# beagle_cnc_1_0.net
KiCad netlist of a schematic drawn in EAGLE
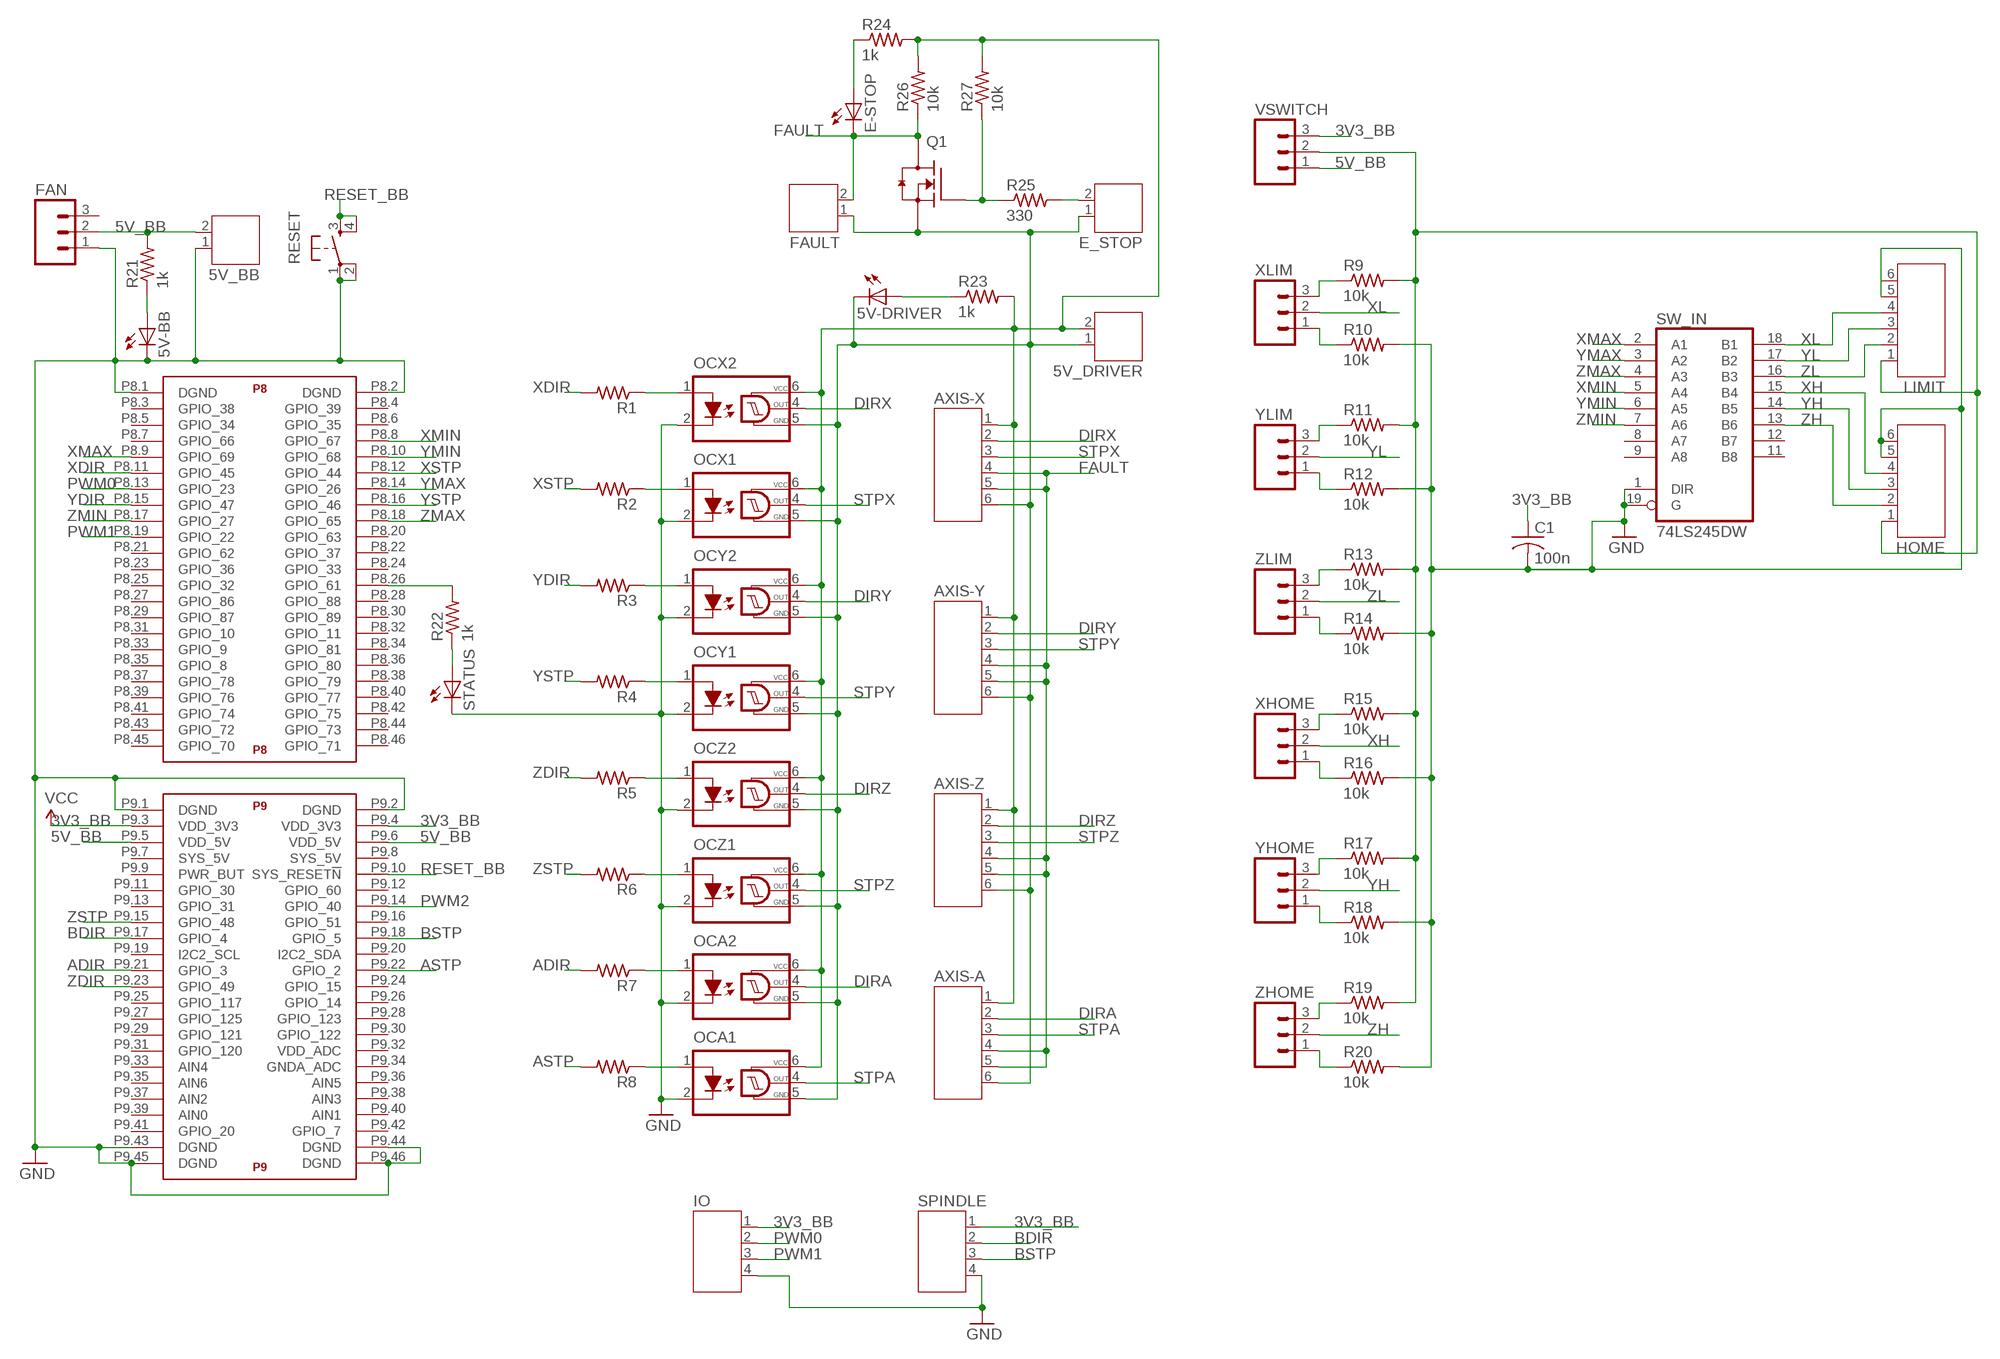
[diagram p0: schematic, sheet 1]

(export (version "E")
  (design (tool "Eeschema 10.0.6"))
  (components
    (comp (ref "5V-BB")
      (value "LEDCHIP-LED0603")
      (footprint "eagle-import:CHIP-LED0603")
      (libsource (lib "eagle-import") (part "LEDCHIP-LED0603"))
    )
    (comp (ref "5V-DRIVER")
      (value "LEDCHIP-LED0603")
      (footprint "eagle-import:CHIP-LED0603")
      (libsource (lib "eagle-import") (part "LEDCHIP-LED0603"))
    )
    (comp (ref "5V_BB")
      (value "JST-PH2")
      (footprint "eagle-import:JST-PH2")
      (libsource (lib "eagle-import") (part "JST-PH2"))
    )
    (comp (ref "5V_DRIVER")
      (value "JST-PH2")
      (footprint "eagle-import:JST-PH2")
      (libsource (lib "eagle-import") (part "JST-PH2"))
    )
    (comp (ref "AXIS-A")
      (value "JST-PH6")
      (footprint "eagle-import:JST-PH6")
      (libsource (lib "eagle-import") (part "JST-PH6"))
    )
    (comp (ref "AXIS-X")
      (value "JST-PH6")
      (footprint "eagle-import:JST-PH6")
      (libsource (lib "eagle-import") (part "JST-PH6"))
    )
    (comp (ref "AXIS-Y")
      (value "JST-PH6")
      (footprint "eagle-import:JST-PH6")
      (libsource (lib "eagle-import") (part "JST-PH6"))
    )
    (comp (ref "AXIS-Z")
      (value "JST-PH6")
      (footprint "eagle-import:JST-PH6")
      (libsource (lib "eagle-import") (part "JST-PH6"))
    )
    (comp (ref "C1")
      (value "100n")
      (footprint "eagle-import:C0603")
      (libsource (lib "eagle-import") (part "C-USC0603"))
    )
    (comp (ref "E-STOP")
      (value "LEDCHIP-LED0603")
      (footprint "eagle-import:CHIP-LED0603")
      (libsource (lib "eagle-import") (part "LEDCHIP-LED0603"))
    )
    (comp (ref "E_STOP")
      (value "JST-PH2")
      (footprint "eagle-import:JST-PH2")
      (libsource (lib "eagle-import") (part "JST-PH2"))
    )
    (comp (ref "FAN")
      (value "M03POLAR")
      (footprint "eagle-import:MOLEX-1X3")
      (libsource (lib "eagle-import") (part "M03POLAR"))
    )
    (comp (ref "FAULT")
      (value "JST-PH2")
      (footprint "eagle-import:JST-PH2")
      (libsource (lib "eagle-import") (part "JST-PH2"))
    )
    (comp (ref "HOME")
      (value "JST-PH6")
      (footprint "eagle-import:JST-PH6")
      (libsource (lib "eagle-import") (part "JST-PH6"))
    )
    (comp (ref "IO")
      (value "JST-PH4")
      (footprint "eagle-import:JST-PH4")
      (libsource (lib "eagle-import") (part "JST-PH4"))
    )
    (comp (ref "LIMIT")
      (value "JST-PH6")
      (footprint "eagle-import:JST-PH6")
      (libsource (lib "eagle-import") (part "JST-PH6"))
    )
    (comp (ref "OCA1")
      (value "H11L1MS")
      (footprint "eagle-import:DIL6-SMD")
      (libsource (lib "eagle-import") (part "H11LMS1"))
    )
    (comp (ref "OCA2")
      (value "H11L1MS")
      (footprint "eagle-import:DIL6-SMD")
      (libsource (lib "eagle-import") (part "H11LMS1"))
    )
    (comp (ref "OCX1")
      (value "H11L1MS")
      (footprint "eagle-import:DIL6-SMD")
      (libsource (lib "eagle-import") (part "H11LMS1"))
    )
    (comp (ref "OCX2")
      (value "H11L1MS")
      (footprint "eagle-import:DIL6-SMD")
      (libsource (lib "eagle-import") (part "H11LMS1"))
    )
    (comp (ref "OCY1")
      (value "H11L1MS")
      (footprint "eagle-import:DIL6-SMD")
      (libsource (lib "eagle-import") (part "H11LMS1"))
    )
    (comp (ref "OCY2")
      (value "H11L1MS")
      (footprint "eagle-import:DIL6-SMD")
      (libsource (lib "eagle-import") (part "H11LMS1"))
    )
    (comp (ref "OCZ1")
      (value "H11L1MS")
      (footprint "eagle-import:DIL6-SMD")
      (libsource (lib "eagle-import") (part "H11LMS1"))
    )
    (comp (ref "OCZ2")
      (value "H11L1MS")
      (footprint "eagle-import:DIL6-SMD")
      (libsource (lib "eagle-import") (part "H11LMS1"))
    )
    (comp (ref "Q1")
      (value "MOSFET-NCH_SOT-23")
      (footprint "eagle-import:SOT95P280X135-3N")
      (libsource (lib "eagle-import") (part "MOSFET-NCH_SOT-23"))
    )
    (comp (ref "R1")
      (value "R-US_R0603")
      (footprint "eagle-import:R0603")
      (libsource (lib "eagle-import") (part "R-US_R0603"))
    )
    (comp (ref "R2")
      (value "R-US_R0603")
      (footprint "eagle-import:R0603")
      (libsource (lib "eagle-import") (part "R-US_R0603"))
    )
    (comp (ref "R3")
      (value "R-US_R0603")
      (footprint "eagle-import:R0603")
      (libsource (lib "eagle-import") (part "R-US_R0603"))
    )
    (comp (ref "R4")
      (value "R-US_R0603")
      (footprint "eagle-import:R0603")
      (libsource (lib "eagle-import") (part "R-US_R0603"))
    )
    (comp (ref "R5")
      (value "R-US_R0603")
      (footprint "eagle-import:R0603")
      (libsource (lib "eagle-import") (part "R-US_R0603"))
    )
    (comp (ref "R6")
      (value "R-US_R0603")
      (footprint "eagle-import:R0603")
      (libsource (lib "eagle-import") (part "R-US_R0603"))
    )
    (comp (ref "R7")
      (value "R-US_R0603")
      (footprint "eagle-import:R0603")
      (libsource (lib "eagle-import") (part "R-US_R0603"))
    )
    (comp (ref "R8")
      (value "R-US_R0603")
      (footprint "eagle-import:R0603")
      (libsource (lib "eagle-import") (part "R-US_R0603"))
    )
    (comp (ref "R9")
      (value "10k")
      (footprint "eagle-import:R0603")
      (libsource (lib "eagle-import") (part "R-US_R0603"))
    )
    (comp (ref "R10")
      (value "10k")
      (footprint "eagle-import:R0603")
      (libsource (lib "eagle-import") (part "R-US_R0603"))
    )
    (comp (ref "R11")
      (value "10k")
      (footprint "eagle-import:R0603")
      (libsource (lib "eagle-import") (part "R-US_R0603"))
    )
    (comp (ref "R12")
      (value "10k")
      (footprint "eagle-import:R0603")
      (libsource (lib "eagle-import") (part "R-US_R0603"))
    )
    (comp (ref "R13")
      (value "10k")
      (footprint "eagle-import:R0603")
      (libsource (lib "eagle-import") (part "R-US_R0603"))
    )
    (comp (ref "R14")
      (value "10k")
      (footprint "eagle-import:R0603")
      (libsource (lib "eagle-import") (part "R-US_R0603"))
    )
    (comp (ref "R15")
      (value "10k")
      (footprint "eagle-import:R0603")
      (libsource (lib "eagle-import") (part "R-US_R0603"))
    )
    (comp (ref "R16")
      (value "10k")
      (footprint "eagle-import:R0603")
      (libsource (lib "eagle-import") (part "R-US_R0603"))
    )
    (comp (ref "R17")
      (value "10k")
      (footprint "eagle-import:R0603")
      (libsource (lib "eagle-import") (part "R-US_R0603"))
    )
    (comp (ref "R18")
      (value "10k")
      (footprint "eagle-import:R0603")
      (libsource (lib "eagle-import") (part "R-US_R0603"))
    )
    (comp (ref "R19")
      (value "10k")
      (footprint "eagle-import:R0603")
      (libsource (lib "eagle-import") (part "R-US_R0603"))
    )
    (comp (ref "R20")
      (value "10k")
      (footprint "eagle-import:R0603")
      (libsource (lib "eagle-import") (part "R-US_R0603"))
    )
    (comp (ref "R21")
      (value "1k")
      (footprint "eagle-import:R0603")
      (libsource (lib "eagle-import") (part "R-US_R0603"))
    )
    (comp (ref "R22")
      (value "1k")
      (footprint "eagle-import:R0603")
      (libsource (lib "eagle-import") (part "R-US_R0603"))
    )
    (comp (ref "R23")
      (value "1k")
      (footprint "eagle-import:R0603")
      (libsource (lib "eagle-import") (part "R-US_R0603"))
    )
    (comp (ref "R24")
      (value "1k")
      (footprint "eagle-import:R0603")
      (libsource (lib "eagle-import") (part "R-US_R0603"))
    )
    (comp (ref "R25")
      (value "330")
      (footprint "eagle-import:R0603")
      (libsource (lib "eagle-import") (part "R-US_R0603"))
    )
    (comp (ref "R26")
      (value "10k")
      (footprint "eagle-import:R0603")
      (libsource (lib "eagle-import") (part "R-US_R0603"))
    )
    (comp (ref "R27")
      (value "10k")
      (footprint "eagle-import:R0603")
      (libsource (lib "eagle-import") (part "R-US_R0603"))
    )
    (comp (ref "RESET")
      (value "TAC_SWITCHSMD")
      (footprint "eagle-import:TACTILE-SWITCH-SMD")
      (libsource (lib "eagle-import") (part "TAC_SWITCHSMD"))
    )
    (comp (ref "SPINDLE")
      (value "JST-PH4")
      (footprint "eagle-import:JST-PH4")
      (libsource (lib "eagle-import") (part "JST-PH4"))
    )
    (comp (ref "STATUS")
      (value "LEDCHIP-LED0603")
      (footprint "eagle-import:CHIP-LED0603")
      (libsource (lib "eagle-import") (part "LEDCHIP-LED0603"))
    )
    (comp (ref "SW_IN")
      (value "74LS245DW")
      (footprint "eagle-import:SO20W")
      (libsource (lib "eagle-import") (part "74245DWLS"))
    )
    (comp (ref "U$1")
      (value "BEAGLE_BONE_BLACK_CAPE")
      (footprint "eagle-import:BEAGLE_BONE_BLACK_CAPE")
      (libsource (lib "eagle-import") (part "BEAGLE_BONE_BLACK_CAPE"))
    )
    (comp (ref "VSWITCH")
      (value "M03PTH")
      (footprint "eagle-import:1X03")
      (libsource (lib "eagle-import") (part "M03PTH"))
    )
    (comp (ref "XHOME")
      (value "M03PTH")
      (footprint "eagle-import:1X03")
      (libsource (lib "eagle-import") (part "M03PTH"))
    )
    (comp (ref "XLIM")
      (value "M03PTH")
      (footprint "eagle-import:1X03")
      (libsource (lib "eagle-import") (part "M03PTH"))
    )
    (comp (ref "YHOME")
      (value "M03PTH")
      (footprint "eagle-import:1X03")
      (libsource (lib "eagle-import") (part "M03PTH"))
    )
    (comp (ref "YLIM")
      (value "M03PTH")
      (footprint "eagle-import:1X03")
      (libsource (lib "eagle-import") (part "M03PTH"))
    )
    (comp (ref "ZHOME")
      (value "M03PTH")
      (footprint "eagle-import:1X03")
      (libsource (lib "eagle-import") (part "M03PTH"))
    )
    (comp (ref "ZLIM")
      (value "M03PTH")
      (footprint "eagle-import:1X03")
      (libsource (lib "eagle-import") (part "M03PTH"))
    )
  )
  (nets
    (net (code "1") (name "/5V_BB") (class "Default")
      (node (ref "5V_BB") (pin "2") (pinfunction "2_2") (pintype "passive"))
      (node (ref "FAN") (pin "2") (pinfunction "2_2") (pintype "passive"))
      (node (ref "R21") (pin "2") (pinfunction "2_2") (pintype "passive"))
      (node (ref "U$1") (pin "P9.5") (pinfunction "VDD_5V_P9.5") (pintype "bidirectional"))
      (node (ref "U$1") (pin "P9.6") (pinfunction "VDD_5V_P9.6") (pintype "bidirectional"))
      (node (ref "VSWITCH") (pin "1") (pinfunction "1_1") (pintype "passive"))
    )
    (net (code "2") (name "/ADIR") (class "Default")
      (node (ref "R7") (pin "2") (pinfunction "2_2") (pintype "passive"))
      (node (ref "U$1") (pin "P9.21") (pinfunction "GPIO_3_P9.21") (pintype "bidirectional"))
    )
    (net (code "3") (name "/ASTP") (class "Default")
      (node (ref "R8") (pin "2") (pinfunction "2_2") (pintype "passive"))
      (node (ref "U$1") (pin "P9.22") (pinfunction "GPIO_2_P9.22") (pintype "bidirectional"))
    )
    (net (code "4") (name "/BDIR") (class "Default")
      (node (ref "SPINDLE") (pin "2") (pinfunction "2_2") (pintype "passive"))
      (node (ref "U$1") (pin "P9.17") (pinfunction "GPIO_4_P9.17") (pintype "bidirectional"))
    )
    (net (code "5") (name "/BSTP") (class "Default")
      (node (ref "SPINDLE") (pin "3") (pinfunction "3_3") (pintype "passive"))
      (node (ref "U$1") (pin "P9.18") (pinfunction "GPIO_5_P9.18") (pintype "bidirectional"))
    )
    (net (code "6") (name "/DIRA") (class "Default")
      (node (ref "AXIS-A") (pin "2") (pinfunction "2_2") (pintype "passive"))
      (node (ref "OCA2") (pin "4") (pinfunction "OUT_4") (pintype "output"))
    )
    (net (code "7") (name "/DIRX") (class "Default")
      (node (ref "AXIS-X") (pin "2") (pinfunction "2_2") (pintype "passive"))
      (node (ref "OCX2") (pin "4") (pinfunction "OUT_4") (pintype "output"))
    )
    (net (code "8") (name "/DIRY") (class "Default")
      (node (ref "AXIS-Y") (pin "2") (pinfunction "2_2") (pintype "passive"))
      (node (ref "OCY2") (pin "4") (pinfunction "OUT_4") (pintype "output"))
    )
    (net (code "9") (name "/DIRZ") (class "Default")
      (node (ref "AXIS-Z") (pin "2") (pinfunction "2_2") (pintype "passive"))
      (node (ref "OCZ2") (pin "4") (pinfunction "OUT_4") (pintype "output"))
    )
    (net (code "10") (name "/FAULT") (class "Default")
      (node (ref "AXIS-A") (pin "4") (pinfunction "4_4") (pintype "passive"))
      (node (ref "AXIS-A") (pin "5") (pinfunction "5_5") (pintype "passive"))
      (node (ref "AXIS-X") (pin "4") (pinfunction "4_4") (pintype "passive"))
      (node (ref "AXIS-X") (pin "5") (pinfunction "5_5") (pintype "passive"))
      (node (ref "AXIS-Y") (pin "4") (pinfunction "4_4") (pintype "passive"))
      (node (ref "AXIS-Y") (pin "5") (pinfunction "5_5") (pintype "passive"))
      (node (ref "AXIS-Z") (pin "4") (pinfunction "4_4") (pintype "passive"))
      (node (ref "AXIS-Z") (pin "5") (pinfunction "5_5") (pintype "passive"))
      (node (ref "E-STOP") (pin "C") (pinfunction "C_C") (pintype "passive"))
      (node (ref "FAULT") (pin "2") (pinfunction "2_2") (pintype "passive"))
      (node (ref "Q1") (pin "3") (pinfunction "D_3") (pintype "passive"))
      (node (ref "R26") (pin "1") (pinfunction "1_1") (pintype "passive"))
    )
    (net (code "11") (name "/PWM0") (class "Default")
      (node (ref "IO") (pin "2") (pinfunction "2_2") (pintype "passive"))
      (node (ref "U$1") (pin "P8.13") (pinfunction "GPIO_23_P8.13") (pintype "bidirectional"))
    )
    (net (code "12") (name "/PWM1") (class "Default")
      (node (ref "IO") (pin "3") (pinfunction "3_3") (pintype "passive"))
      (node (ref "U$1") (pin "P8.19") (pinfunction "GPIO_22_P8.19") (pintype "bidirectional"))
    )
    (net (code "13") (name "/PWM2") (class "Default")
      (node (ref "U$1") (pin "P9.14") (pinfunction "GPIO_40_P9.14") (pintype "bidirectional"))
    )
    (net (code "14") (name "/RESET_BB") (class "Default")
      (node (ref "RESET") (pin "3") (pinfunction "3_3") (pintype "passive"))
      (node (ref "RESET") (pin "4") (pinfunction "4_4") (pintype "passive"))
      (node (ref "U$1") (pin "P9.10") (pinfunction "SYS_RESET~{N}_P9.10") (pintype "bidirectional"))
    )
    (net (code "15") (name "/STPA") (class "Default")
      (node (ref "AXIS-A") (pin "3") (pinfunction "3_3") (pintype "passive"))
      (node (ref "OCA1") (pin "4") (pinfunction "OUT_4") (pintype "output"))
    )
    (net (code "16") (name "/STPX") (class "Default")
      (node (ref "AXIS-X") (pin "3") (pinfunction "3_3") (pintype "passive"))
      (node (ref "OCX1") (pin "4") (pinfunction "OUT_4") (pintype "output"))
    )
    (net (code "17") (name "/STPY") (class "Default")
      (node (ref "AXIS-Y") (pin "3") (pinfunction "3_3") (pintype "passive"))
      (node (ref "OCY1") (pin "4") (pinfunction "OUT_4") (pintype "output"))
    )
    (net (code "18") (name "/STPZ") (class "Default")
      (node (ref "AXIS-Z") (pin "3") (pinfunction "3_3") (pintype "passive"))
      (node (ref "OCZ1") (pin "4") (pinfunction "OUT_4") (pintype "output"))
    )
    (net (code "19") (name "/XDIR") (class "Default")
      (node (ref "R1") (pin "2") (pinfunction "2_2") (pintype "passive"))
      (node (ref "U$1") (pin "P8.11") (pinfunction "GPIO_45_P8.11") (pintype "bidirectional"))
    )
    (net (code "20") (name "/XH") (class "Default")
      (node (ref "HOME") (pin "4") (pinfunction "4_4") (pintype "passive"))
      (node (ref "SW_IN") (pin "15") (pinfunction "B4_15") (pintype "bidirectional"))
      (node (ref "XHOME") (pin "2") (pinfunction "2_2") (pintype "passive"))
    )
    (net (code "21") (name "/XL") (class "Default")
      (node (ref "LIMIT") (pin "4") (pinfunction "4_4") (pintype "passive"))
      (node (ref "SW_IN") (pin "18") (pinfunction "B1_18") (pintype "bidirectional"))
      (node (ref "XLIM") (pin "2") (pinfunction "2_2") (pintype "passive"))
    )
    (net (code "22") (name "/XMAX") (class "Default")
      (node (ref "SW_IN") (pin "2") (pinfunction "A1_2") (pintype "bidirectional"))
      (node (ref "U$1") (pin "P8.9") (pinfunction "GPIO_69_P8.9") (pintype "bidirectional"))
    )
    (net (code "23") (name "/XMIN") (class "Default")
      (node (ref "SW_IN") (pin "5") (pinfunction "A4_5") (pintype "bidirectional"))
      (node (ref "U$1") (pin "P8.8") (pinfunction "GPIO_67_P8.8") (pintype "bidirectional"))
    )
    (net (code "24") (name "/XSTP") (class "Default")
      (node (ref "R2") (pin "2") (pinfunction "2_2") (pintype "passive"))
      (node (ref "U$1") (pin "P8.12") (pinfunction "GPIO_44_P8.12") (pintype "bidirectional"))
    )
    (net (code "25") (name "/YDIR") (class "Default")
      (node (ref "R3") (pin "2") (pinfunction "2_2") (pintype "passive"))
      (node (ref "U$1") (pin "P8.15") (pinfunction "GPIO_47_P8.15") (pintype "bidirectional"))
    )
    (net (code "26") (name "/YH") (class "Default")
      (node (ref "HOME") (pin "3") (pinfunction "3_3") (pintype "passive"))
      (node (ref "SW_IN") (pin "14") (pinfunction "B5_14") (pintype "bidirectional"))
      (node (ref "YHOME") (pin "2") (pinfunction "2_2") (pintype "passive"))
    )
    (net (code "27") (name "/YL") (class "Default")
      (node (ref "LIMIT") (pin "3") (pinfunction "3_3") (pintype "passive"))
      (node (ref "SW_IN") (pin "17") (pinfunction "B2_17") (pintype "bidirectional"))
      (node (ref "YLIM") (pin "2") (pinfunction "2_2") (pintype "passive"))
    )
    (net (code "28") (name "/YMAX") (class "Default")
      (node (ref "SW_IN") (pin "3") (pinfunction "A2_3") (pintype "bidirectional"))
      (node (ref "U$1") (pin "P8.14") (pinfunction "GPIO_26_P8.14") (pintype "bidirectional"))
    )
    (net (code "29") (name "/YMIN") (class "Default")
      (node (ref "SW_IN") (pin "6") (pinfunction "A5_6") (pintype "bidirectional"))
      (node (ref "U$1") (pin "P8.10") (pinfunction "GPIO_68_P8.10") (pintype "bidirectional"))
    )
    (net (code "30") (name "/YSTP") (class "Default")
      (node (ref "R4") (pin "2") (pinfunction "2_2") (pintype "passive"))
      (node (ref "U$1") (pin "P8.16") (pinfunction "GPIO_46_P8.16") (pintype "bidirectional"))
    )
    (net (code "31") (name "/ZDIR") (class "Default")
      (node (ref "R5") (pin "2") (pinfunction "2_2") (pintype "passive"))
      (node (ref "U$1") (pin "P9.23") (pinfunction "GPIO_49_P9.23") (pintype "bidirectional"))
    )
    (net (code "32") (name "/ZH") (class "Default")
      (node (ref "HOME") (pin "2") (pinfunction "2_2") (pintype "passive"))
      (node (ref "SW_IN") (pin "13") (pinfunction "B6_13") (pintype "bidirectional"))
      (node (ref "ZHOME") (pin "2") (pinfunction "2_2") (pintype "passive"))
    )
    (net (code "33") (name "/ZL") (class "Default")
      (node (ref "LIMIT") (pin "2") (pinfunction "2_2") (pintype "passive"))
      (node (ref "SW_IN") (pin "16") (pinfunction "B3_16") (pintype "bidirectional"))
      (node (ref "ZLIM") (pin "2") (pinfunction "2_2") (pintype "passive"))
    )
    (net (code "34") (name "/ZMAX") (class "Default")
      (node (ref "SW_IN") (pin "4") (pinfunction "A3_4") (pintype "bidirectional"))
      (node (ref "U$1") (pin "P8.18") (pinfunction "GPIO_65_P8.18") (pintype "bidirectional"))
    )
    (net (code "35") (name "/ZMIN") (class "Default")
      (node (ref "SW_IN") (pin "7") (pinfunction "A6_7") (pintype "bidirectional"))
      (node (ref "U$1") (pin "P8.17") (pinfunction "GPIO_27_P8.17") (pintype "bidirectional"))
    )
    (net (code "36") (name "/ZSTP") (class "Default")
      (node (ref "R6") (pin "2") (pinfunction "2_2") (pintype "passive"))
      (node (ref "U$1") (pin "P9.15") (pinfunction "GPIO_48_P9.15") (pintype "bidirectional"))
    )
    (net (code "37") (name "GND") (class "Default")
      (node (ref "5V-BB") (pin "C") (pinfunction "C_C") (pintype "passive"))
      (node (ref "5V_BB") (pin "1") (pinfunction "1_1") (pintype "passive"))
      (node (ref "C1") (pin "2") (pinfunction "2_2") (pintype "passive"))
      (node (ref "FAN") (pin "1") (pinfunction "1_1") (pintype "passive"))
      (node (ref "HOME") (pin "5") (pinfunction "5_5") (pintype "passive"))
      (node (ref "HOME") (pin "6") (pinfunction "6_6") (pintype "passive"))
      (node (ref "IO") (pin "4") (pinfunction "4_4") (pintype "passive"))
      (node (ref "LIMIT") (pin "5") (pinfunction "5_5") (pintype "passive"))
      (node (ref "LIMIT") (pin "6") (pinfunction "6_6") (pintype "passive"))
      (node (ref "OCA1") (pin "2") (pinfunction "C_2") (pintype "passive"))
      (node (ref "OCA2") (pin "2") (pinfunction "C_2") (pintype "passive"))
      (node (ref "OCX1") (pin "2") (pinfunction "C_2") (pintype "passive"))
      (node (ref "OCX2") (pin "2") (pinfunction "C_2") (pintype "passive"))
      (node (ref "OCY1") (pin "2") (pinfunction "C_2") (pintype "passive"))
      (node (ref "OCY2") (pin "2") (pinfunction "C_2") (pintype "passive"))
      (node (ref "OCZ1") (pin "2") (pinfunction "C_2") (pintype "passive"))
      (node (ref "OCZ2") (pin "2") (pinfunction "C_2") (pintype "passive"))
      (node (ref "R10") (pin "2") (pinfunction "2_2") (pintype "passive"))
      (node (ref "R12") (pin "2") (pinfunction "2_2") (pintype "passive"))
      (node (ref "R14") (pin "2") (pinfunction "2_2") (pintype "passive"))
      (node (ref "R16") (pin "2") (pinfunction "2_2") (pintype "passive"))
      (node (ref "R18") (pin "2") (pinfunction "2_2") (pintype "passive"))
      (node (ref "R20") (pin "2") (pinfunction "2_2") (pintype "passive"))
      (node (ref "RESET") (pin "1") (pinfunction "1_1") (pintype "passive"))
      (node (ref "RESET") (pin "2") (pinfunction "2_2") (pintype "passive"))
      (node (ref "SPINDLE") (pin "4") (pinfunction "4_4") (pintype "passive"))
      (node (ref "STATUS") (pin "C") (pinfunction "C_C") (pintype "passive"))
      (node (ref "SW_IN") (pin "1") (pinfunction "DIR_1") (pintype "input"))
      (node (ref "SW_IN") (pin "19") (pinfunction "G_19") (pintype "input"))
      (node (ref "U$1") (pin "P8.1") (pinfunction "DGND_P8.1") (pintype "bidirectional"))
      (node (ref "U$1") (pin "P8.2") (pinfunction "DGND_P8.2") (pintype "bidirectional"))
      (node (ref "U$1") (pin "P9.1") (pinfunction "DGND_P9.1") (pintype "bidirectional"))
      (node (ref "U$1") (pin "P9.2") (pinfunction "DGND_P9.2") (pintype "bidirectional"))
      (node (ref "U$1") (pin "P9.43") (pinfunction "DGND_P9.43") (pintype "bidirectional"))
      (node (ref "U$1") (pin "P9.44") (pinfunction "DGND_P9.44") (pintype "bidirectional"))
      (node (ref "U$1") (pin "P9.45") (pinfunction "DGND_P9.45") (pintype "bidirectional"))
      (node (ref "U$1") (pin "P9.46") (pinfunction "DGND_P9.46") (pintype "bidirectional"))
    )
    (net (code "38") (name "Net-(5V-BB-PadA)") (class "Default")
      (node (ref "5V-BB") (pin "A") (pinfunction "A_A") (pintype "passive"))
      (node (ref "R21") (pin "1") (pinfunction "1_1") (pintype "passive"))
    )
    (net (code "39") (name "Net-(5V-DRIVER-PadA)") (class "Default")
      (node (ref "5V-DRIVER") (pin "A") (pinfunction "A_A") (pintype "passive"))
      (node (ref "R23") (pin "1") (pinfunction "1_1") (pintype "passive"))
    )
    (net (code "40") (name "Net-(E-STOP-PadA)") (class "Default")
      (node (ref "E-STOP") (pin "A") (pinfunction "A_A") (pintype "passive"))
      (node (ref "R24") (pin "1") (pinfunction "1_1") (pintype "passive"))
    )
    (net (code "41") (name "Net-(E_STOP-Pad2)") (class "Default")
      (node (ref "E_STOP") (pin "2") (pinfunction "2_2") (pintype "passive"))
      (node (ref "R25") (pin "2") (pinfunction "2_2") (pintype "passive"))
    )
    (net (code "42") (name "Net-(HOME-Pad1)") (class "Default")
      (node (ref "HOME") (pin "1") (pinfunction "1_1") (pintype "passive"))
      (node (ref "LIMIT") (pin "1") (pinfunction "1_1") (pintype "passive"))
      (node (ref "R11") (pin "2") (pinfunction "2_2") (pintype "passive"))
      (node (ref "R13") (pin "2") (pinfunction "2_2") (pintype "passive"))
      (node (ref "R15") (pin "2") (pinfunction "2_2") (pintype "passive"))
      (node (ref "R17") (pin "2") (pinfunction "2_2") (pintype "passive"))
      (node (ref "R19") (pin "2") (pinfunction "2_2") (pintype "passive"))
      (node (ref "R9") (pin "2") (pinfunction "2_2") (pintype "passive"))
      (node (ref "VSWITCH") (pin "2") (pinfunction "2_2") (pintype "passive"))
    )
    (net (code "43") (name "Net-(OCA1-A)") (class "Default")
      (node (ref "OCA1") (pin "1") (pinfunction "A_1") (pintype "passive"))
      (node (ref "R8") (pin "1") (pinfunction "1_1") (pintype "passive"))
    )
    (net (code "44") (name "Net-(OCA1-GND)") (class "Default")
      (node (ref "5V-DRIVER") (pin "C") (pinfunction "C_C") (pintype "passive"))
      (node (ref "5V_DRIVER") (pin "1") (pinfunction "1_1") (pintype "passive"))
      (node (ref "AXIS-A") (pin "6") (pinfunction "6_6") (pintype "passive"))
      (node (ref "AXIS-X") (pin "6") (pinfunction "6_6") (pintype "passive"))
      (node (ref "AXIS-Y") (pin "6") (pinfunction "6_6") (pintype "passive"))
      (node (ref "AXIS-Z") (pin "6") (pinfunction "6_6") (pintype "passive"))
      (node (ref "E_STOP") (pin "1") (pinfunction "1_1") (pintype "passive"))
      (node (ref "FAULT") (pin "1") (pinfunction "1_1") (pintype "passive"))
      (node (ref "OCA1") (pin "5") (pinfunction "GND_5") (pintype "power_in"))
      (node (ref "OCA2") (pin "5") (pinfunction "GND_5") (pintype "power_in"))
      (node (ref "OCX1") (pin "5") (pinfunction "GND_5") (pintype "power_in"))
      (node (ref "OCX2") (pin "5") (pinfunction "GND_5") (pintype "power_in"))
      (node (ref "OCY1") (pin "5") (pinfunction "GND_5") (pintype "power_in"))
      (node (ref "OCY2") (pin "5") (pinfunction "GND_5") (pintype "power_in"))
      (node (ref "OCZ1") (pin "5") (pinfunction "GND_5") (pintype "power_in"))
      (node (ref "OCZ2") (pin "5") (pinfunction "GND_5") (pintype "power_in"))
      (node (ref "Q1") (pin "2") (pinfunction "S_2") (pintype "passive"))
    )
    (net (code "45") (name "Net-(OCA1-VCC)") (class "Default")
      (node (ref "5V_DRIVER") (pin "2") (pinfunction "2_2") (pintype "passive"))
      (node (ref "AXIS-A") (pin "1") (pinfunction "1_1") (pintype "passive"))
      (node (ref "AXIS-X") (pin "1") (pinfunction "1_1") (pintype "passive"))
      (node (ref "AXIS-Y") (pin "1") (pinfunction "1_1") (pintype "passive"))
      (node (ref "AXIS-Z") (pin "1") (pinfunction "1_1") (pintype "passive"))
      (node (ref "OCA1") (pin "6") (pinfunction "VCC_6") (pintype "power_in"))
      (node (ref "OCA2") (pin "6") (pinfunction "VCC_6") (pintype "power_in"))
      (node (ref "OCX1") (pin "6") (pinfunction "VCC_6") (pintype "power_in"))
      (node (ref "OCX2") (pin "6") (pinfunction "VCC_6") (pintype "power_in"))
      (node (ref "OCY1") (pin "6") (pinfunction "VCC_6") (pintype "power_in"))
      (node (ref "OCY2") (pin "6") (pinfunction "VCC_6") (pintype "power_in"))
      (node (ref "OCZ1") (pin "6") (pinfunction "VCC_6") (pintype "power_in"))
      (node (ref "OCZ2") (pin "6") (pinfunction "VCC_6") (pintype "power_in"))
      (node (ref "R23") (pin "2") (pinfunction "2_2") (pintype "passive"))
      (node (ref "R24") (pin "2") (pinfunction "2_2") (pintype "passive"))
      (node (ref "R26") (pin "2") (pinfunction "2_2") (pintype "passive"))
      (node (ref "R27") (pin "2") (pinfunction "2_2") (pintype "passive"))
    )
    (net (code "46") (name "Net-(OCA2-A)") (class "Default")
      (node (ref "OCA2") (pin "1") (pinfunction "A_1") (pintype "passive"))
      (node (ref "R7") (pin "1") (pinfunction "1_1") (pintype "passive"))
    )
    (net (code "47") (name "Net-(OCX1-A)") (class "Default")
      (node (ref "OCX1") (pin "1") (pinfunction "A_1") (pintype "passive"))
      (node (ref "R2") (pin "1") (pinfunction "1_1") (pintype "passive"))
    )
    (net (code "48") (name "Net-(OCX2-A)") (class "Default")
      (node (ref "OCX2") (pin "1") (pinfunction "A_1") (pintype "passive"))
      (node (ref "R1") (pin "1") (pinfunction "1_1") (pintype "passive"))
    )
    (net (code "49") (name "Net-(OCY1-A)") (class "Default")
      (node (ref "OCY1") (pin "1") (pinfunction "A_1") (pintype "passive"))
      (node (ref "R4") (pin "1") (pinfunction "1_1") (pintype "passive"))
    )
    (net (code "50") (name "Net-(OCY2-A)") (class "Default")
      (node (ref "OCY2") (pin "1") (pinfunction "A_1") (pintype "passive"))
      (node (ref "R3") (pin "1") (pinfunction "1_1") (pintype "passive"))
    )
    (net (code "51") (name "Net-(OCZ1-A)") (class "Default")
      (node (ref "OCZ1") (pin "1") (pinfunction "A_1") (pintype "passive"))
      (node (ref "R6") (pin "1") (pinfunction "1_1") (pintype "passive"))
    )
    (net (code "52") (name "Net-(OCZ2-A)") (class "Default")
      (node (ref "OCZ2") (pin "1") (pinfunction "A_1") (pintype "passive"))
      (node (ref "R5") (pin "1") (pinfunction "1_1") (pintype "passive"))
    )
    (net (code "53") (name "Net-(Q1-G)") (class "Default")
      (node (ref "Q1") (pin "1") (pinfunction "G_1") (pintype "passive"))
      (node (ref "R25") (pin "1") (pinfunction "1_1") (pintype "passive"))
      (node (ref "R27") (pin "1") (pinfunction "1_1") (pintype "passive"))
    )
    (net (code "54") (name "Net-(R9-Pad1)") (class "Default")
      (node (ref "R9") (pin "1") (pinfunction "1_1") (pintype "passive"))
      (node (ref "XLIM") (pin "3") (pinfunction "3_3") (pintype "passive"))
    )
    (net (code "55") (name "Net-(R10-Pad1)") (class "Default")
      (node (ref "R10") (pin "1") (pinfunction "1_1") (pintype "passive"))
      (node (ref "XLIM") (pin "1") (pinfunction "1_1") (pintype "passive"))
    )
    (net (code "56") (name "Net-(R11-Pad1)") (class "Default")
      (node (ref "R11") (pin "1") (pinfunction "1_1") (pintype "passive"))
      (node (ref "YLIM") (pin "3") (pinfunction "3_3") (pintype "passive"))
    )
    (net (code "57") (name "Net-(R12-Pad1)") (class "Default")
      (node (ref "R12") (pin "1") (pinfunction "1_1") (pintype "passive"))
      (node (ref "YLIM") (pin "1") (pinfunction "1_1") (pintype "passive"))
    )
    (net (code "58") (name "Net-(R13-Pad1)") (class "Default")
      (node (ref "R13") (pin "1") (pinfunction "1_1") (pintype "passive"))
      (node (ref "ZLIM") (pin "3") (pinfunction "3_3") (pintype "passive"))
    )
    (net (code "59") (name "Net-(R14-Pad1)") (class "Default")
      (node (ref "R14") (pin "1") (pinfunction "1_1") (pintype "passive"))
      (node (ref "ZLIM") (pin "1") (pinfunction "1_1") (pintype "passive"))
    )
    (net (code "60") (name "Net-(R15-Pad1)") (class "Default")
      (node (ref "R15") (pin "1") (pinfunction "1_1") (pintype "passive"))
      (node (ref "XHOME") (pin "3") (pinfunction "3_3") (pintype "passive"))
    )
    (net (code "61") (name "Net-(R16-Pad1)") (class "Default")
      (node (ref "R16") (pin "1") (pinfunction "1_1") (pintype "passive"))
      (node (ref "XHOME") (pin "1") (pinfunction "1_1") (pintype "passive"))
    )
    (net (code "62") (name "Net-(R17-Pad1)") (class "Default")
      (node (ref "R17") (pin "1") (pinfunction "1_1") (pintype "passive"))
      (node (ref "YHOME") (pin "3") (pinfunction "3_3") (pintype "passive"))
    )
    (net (code "63") (name "Net-(R18-Pad1)") (class "Default")
      (node (ref "R18") (pin "1") (pinfunction "1_1") (pintype "passive"))
      (node (ref "YHOME") (pin "1") (pinfunction "1_1") (pintype "passive"))
    )
    (net (code "64") (name "Net-(R19-Pad1)") (class "Default")
      (node (ref "R19") (pin "1") (pinfunction "1_1") (pintype "passive"))
      (node (ref "ZHOME") (pin "3") (pinfunction "3_3") (pintype "passive"))
    )
    (net (code "65") (name "Net-(R20-Pad1)") (class "Default")
      (node (ref "R20") (pin "1") (pinfunction "1_1") (pintype "passive"))
      (node (ref "ZHOME") (pin "1") (pinfunction "1_1") (pintype "passive"))
    )
    (net (code "66") (name "Net-(R22-Pad1)") (class "Default")
      (node (ref "R22") (pin "1") (pinfunction "1_1") (pintype "passive"))
      (node (ref "STATUS") (pin "A") (pinfunction "A_A") (pintype "passive"))
    )
    (net (code "67") (name "Net-(U$1A-GPIO_61)") (class "Default")
      (node (ref "R22") (pin "2") (pinfunction "2_2") (pintype "passive"))
      (node (ref "U$1") (pin "P8.26") (pinfunction "GPIO_61_P8.26") (pintype "bidirectional"))
    )
    (net (code "68") (name "VCC") (class "Default")
      (node (ref "C1") (pin "1") (pinfunction "1_1") (pintype "passive"))
      (node (ref "IO") (pin "1") (pinfunction "1_1") (pintype "passive"))
      (node (ref "SPINDLE") (pin "1") (pinfunction "1_1") (pintype "passive"))
      (node (ref "U$1") (pin "P9.3") (pinfunction "VDD_3V3_P9.3") (pintype "bidirectional"))
      (node (ref "U$1") (pin "P9.4") (pinfunction "VDD_3V3_P9.4") (pintype "bidirectional"))
      (node (ref "VSWITCH") (pin "3") (pinfunction "3_3") (pintype "passive"))
    )
    (net (code "69") (name "unconnected-(FAN-Pad3)") (class "Default")
      (node (ref "FAN") (pin "3") (pinfunction "3_3") (pintype "passive"))
    )
    (net (code "70") (name "unconnected-(SW_INA-A7-Pad8)") (class "Default")
      (node (ref "SW_IN") (pin "8") (pinfunction "A7_8") (pintype "bidirectional"))
    )
    (net (code "71") (name "unconnected-(SW_INA-A8-Pad9)") (class "Default")
      (node (ref "SW_IN") (pin "9") (pinfunction "A8_9") (pintype "bidirectional"))
    )
    (net (code "72") (name "unconnected-(SW_INA-B7-Pad12)") (class "Default")
      (node (ref "SW_IN") (pin "12") (pinfunction "B7_12") (pintype "bidirectional"))
    )
    (net (code "73") (name "unconnected-(SW_INA-B8-Pad11)") (class "Default")
      (node (ref "SW_IN") (pin "11") (pinfunction "B8_11") (pintype "bidirectional"))
    )
    (net (code "74") (name "unconnected-(U$1A-GPIO_8-PadP8.35)") (class "Default")
      (node (ref "U$1") (pin "P8.35") (pinfunction "GPIO_8_P8.35") (pintype "bidirectional"))
    )
    (net (code "75") (name "unconnected-(U$1A-GPIO_9-PadP8.33)") (class "Default")
      (node (ref "U$1") (pin "P8.33") (pinfunction "GPIO_9_P8.33") (pintype "bidirectional"))
    )
    (net (code "76") (name "unconnected-(U$1A-GPIO_10-PadP8.31)") (class "Default")
      (node (ref "U$1") (pin "P8.31") (pinfunction "GPIO_10_P8.31") (pintype "bidirectional"))
    )
    (net (code "77") (name "unconnected-(U$1A-GPIO_11-PadP8.32)") (class "Default")
      (node (ref "U$1") (pin "P8.32") (pinfunction "GPIO_11_P8.32") (pintype "bidirectional"))
    )
    (net (code "78") (name "unconnected-(U$1A-GPIO_32-PadP8.25)") (class "Default")
      (node (ref "U$1") (pin "P8.25") (pinfunction "GPIO_32_P8.25") (pintype "bidirectional"))
    )
    (net (code "79") (name "unconnected-(U$1A-GPIO_33-PadP8.24)") (class "Default")
      (node (ref "U$1") (pin "P8.24") (pinfunction "GPIO_33_P8.24") (pintype "bidirectional"))
    )
    (net (code "80") (name "unconnected-(U$1A-GPIO_34-PadP8.5)") (class "Default")
      (node (ref "U$1") (pin "P8.5") (pinfunction "GPIO_34_P8.5") (pintype "bidirectional"))
    )
    (net (code "81") (name "unconnected-(U$1A-GPIO_35-PadP8.6)") (class "Default")
      (node (ref "U$1") (pin "P8.6") (pinfunction "GPIO_35_P8.6") (pintype "bidirectional"))
    )
    (net (code "82") (name "unconnected-(U$1A-GPIO_36-PadP8.23)") (class "Default")
      (node (ref "U$1") (pin "P8.23") (pinfunction "GPIO_36_P8.23") (pintype "bidirectional"))
    )
    (net (code "83") (name "unconnected-(U$1A-GPIO_37-PadP8.22)") (class "Default")
      (node (ref "U$1") (pin "P8.22") (pinfunction "GPIO_37_P8.22") (pintype "bidirectional"))
    )
    (net (code "84") (name "unconnected-(U$1A-GPIO_38-PadP8.3)") (class "Default")
      (node (ref "U$1") (pin "P8.3") (pinfunction "GPIO_38_P8.3") (pintype "bidirectional"))
    )
    (net (code "85") (name "unconnected-(U$1A-GPIO_39-PadP8.4)") (class "Default")
      (node (ref "U$1") (pin "P8.4") (pinfunction "GPIO_39_P8.4") (pintype "bidirectional"))
    )
    (net (code "86") (name "unconnected-(U$1A-GPIO_62-PadP8.21)") (class "Default")
      (node (ref "U$1") (pin "P8.21") (pinfunction "GPIO_62_P8.21") (pintype "bidirectional"))
    )
    (net (code "87") (name "unconnected-(U$1A-GPIO_63-PadP8.20)") (class "Default")
      (node (ref "U$1") (pin "P8.20") (pinfunction "GPIO_63_P8.20") (pintype "bidirectional"))
    )
    (net (code "88") (name "unconnected-(U$1A-GPIO_66-PadP8.7)") (class "Default")
      (node (ref "U$1") (pin "P8.7") (pinfunction "GPIO_66_P8.7") (pintype "bidirectional"))
    )
    (net (code "89") (name "unconnected-(U$1A-GPIO_70-PadP8.45)") (class "Default")
      (node (ref "U$1") (pin "P8.45") (pinfunction "GPIO_70_P8.45") (pintype "bidirectional"))
    )
    (net (code "90") (name "unconnected-(U$1A-GPIO_71-PadP8.46)") (class "Default")
      (node (ref "U$1") (pin "P8.46") (pinfunction "GPIO_71_P8.46") (pintype "bidirectional"))
    )
    (net (code "91") (name "unconnected-(U$1A-GPIO_72-PadP8.43)") (class "Default")
      (node (ref "U$1") (pin "P8.43") (pinfunction "GPIO_72_P8.43") (pintype "bidirectional"))
    )
    (net (code "92") (name "unconnected-(U$1A-GPIO_73-PadP8.44)") (class "Default")
      (node (ref "U$1") (pin "P8.44") (pinfunction "GPIO_73_P8.44") (pintype "bidirectional"))
    )
    (net (code "93") (name "unconnected-(U$1A-GPIO_74-PadP8.41)") (class "Default")
      (node (ref "U$1") (pin "P8.41") (pinfunction "GPIO_74_P8.41") (pintype "bidirectional"))
    )
    (net (code "94") (name "unconnected-(U$1A-GPIO_75-PadP8.42)") (class "Default")
      (node (ref "U$1") (pin "P8.42") (pinfunction "GPIO_75_P8.42") (pintype "bidirectional"))
    )
    (net (code "95") (name "unconnected-(U$1A-GPIO_76-PadP8.39)") (class "Default")
      (node (ref "U$1") (pin "P8.39") (pinfunction "GPIO_76_P8.39") (pintype "bidirectional"))
    )
    (net (code "96") (name "unconnected-(U$1A-GPIO_77-PadP8.40)") (class "Default")
      (node (ref "U$1") (pin "P8.40") (pinfunction "GPIO_77_P8.40") (pintype "bidirectional"))
    )
    (net (code "97") (name "unconnected-(U$1A-GPIO_78-PadP8.37)") (class "Default")
      (node (ref "U$1") (pin "P8.37") (pinfunction "GPIO_78_P8.37") (pintype "bidirectional"))
    )
    (net (code "98") (name "unconnected-(U$1A-GPIO_79-PadP8.38)") (class "Default")
      (node (ref "U$1") (pin "P8.38") (pinfunction "GPIO_79_P8.38") (pintype "bidirectional"))
    )
    (net (code "99") (name "unconnected-(U$1A-GPIO_80-PadP8.36)") (class "Default")
      (node (ref "U$1") (pin "P8.36") (pinfunction "GPIO_80_P8.36") (pintype "bidirectional"))
    )
    (net (code "100") (name "unconnected-(U$1A-GPIO_81-PadP8.34)") (class "Default")
      (node (ref "U$1") (pin "P8.34") (pinfunction "GPIO_81_P8.34") (pintype "bidirectional"))
    )
    (net (code "101") (name "unconnected-(U$1A-GPIO_86-PadP8.27)") (class "Default")
      (node (ref "U$1") (pin "P8.27") (pinfunction "GPIO_86_P8.27") (pintype "bidirectional"))
    )
    (net (code "102") (name "unconnected-(U$1A-GPIO_87-PadP8.29)") (class "Default")
      (node (ref "U$1") (pin "P8.29") (pinfunction "GPIO_87_P8.29") (pintype "bidirectional"))
    )
    (net (code "103") (name "unconnected-(U$1A-GPIO_88-PadP8.28)") (class "Default")
      (node (ref "U$1") (pin "P8.28") (pinfunction "GPIO_88_P8.28") (pintype "bidirectional"))
    )
    (net (code "104") (name "unconnected-(U$1A-GPIO_89-PadP8.30)") (class "Default")
      (node (ref "U$1") (pin "P8.30") (pinfunction "GPIO_89_P8.30") (pintype "bidirectional"))
    )
    (net (code "105") (name "unconnected-(U$1B-AIN0-PadP9.39)") (class "Default")
      (node (ref "U$1") (pin "P9.39") (pinfunction "AIN0_P9.39") (pintype "bidirectional"))
    )
    (net (code "106") (name "unconnected-(U$1B-AIN1-PadP9.40)") (class "Default")
      (node (ref "U$1") (pin "P9.40") (pinfunction "AIN1_P9.40") (pintype "bidirectional"))
    )
    (net (code "107") (name "unconnected-(U$1B-AIN2-PadP9.37)") (class "Default")
      (node (ref "U$1") (pin "P9.37") (pinfunction "AIN2_P9.37") (pintype "bidirectional"))
    )
    (net (code "108") (name "unconnected-(U$1B-AIN3-PadP9.38)") (class "Default")
      (node (ref "U$1") (pin "P9.38") (pinfunction "AIN3_P9.38") (pintype "bidirectional"))
    )
    (net (code "109") (name "unconnected-(U$1B-AIN4-PadP9.33)") (class "Default")
      (node (ref "U$1") (pin "P9.33") (pinfunction "AIN4_P9.33") (pintype "bidirectional"))
    )
    (net (code "110") (name "unconnected-(U$1B-AIN5-PadP9.36)") (class "Default")
      (node (ref "U$1") (pin "P9.36") (pinfunction "AIN5_P9.36") (pintype "bidirectional"))
    )
    (net (code "111") (name "unconnected-(U$1B-AIN6-PadP9.35)") (class "Default")
      (node (ref "U$1") (pin "P9.35") (pinfunction "AIN6_P9.35") (pintype "bidirectional"))
    )
    (net (code "112") (name "unconnected-(U$1B-GNDA_ADC-PadP9.34)") (class "Default")
      (node (ref "U$1") (pin "P9.34") (pinfunction "GNDA_ADC_P9.34") (pintype "bidirectional"))
    )
    (net (code "113") (name "unconnected-(U$1B-GPIO_7-PadP9.42)") (class "Default")
      (node (ref "U$1") (pin "P9.42") (pinfunction "GPIO_7_P9.42") (pintype "bidirectional"))
    )
    (net (code "114") (name "unconnected-(U$1B-GPIO_14-PadP9.26)") (class "Default")
      (node (ref "U$1") (pin "P9.26") (pinfunction "GPIO_14_P9.26") (pintype "bidirectional"))
    )
    (net (code "115") (name "unconnected-(U$1B-GPIO_15-PadP9.24)") (class "Default")
      (node (ref "U$1") (pin "P9.24") (pinfunction "GPIO_15_P9.24") (pintype "bidirectional"))
    )
    (net (code "116") (name "unconnected-(U$1B-GPIO_20-PadP9.41)") (class "Default")
      (node (ref "U$1") (pin "P9.41") (pinfunction "GPIO_20_P9.41") (pintype "bidirectional"))
    )
    (net (code "117") (name "unconnected-(U$1B-GPIO_30-PadP9.11)") (class "Default")
      (node (ref "U$1") (pin "P9.11") (pinfunction "GPIO_30_P9.11") (pintype "bidirectional"))
    )
    (net (code "118") (name "unconnected-(U$1B-GPIO_31-PadP9.13)") (class "Default")
      (node (ref "U$1") (pin "P9.13") (pinfunction "GPIO_31_P9.13") (pintype "bidirectional"))
    )
    (net (code "119") (name "unconnected-(U$1B-GPIO_51-PadP9.16)") (class "Default")
      (node (ref "U$1") (pin "P9.16") (pinfunction "GPIO_51_P9.16") (pintype "bidirectional"))
    )
    (net (code "120") (name "unconnected-(U$1B-GPIO_60-PadP9.12)") (class "Default")
      (node (ref "U$1") (pin "P9.12") (pinfunction "GPIO_60_P9.12") (pintype "bidirectional"))
    )
    (net (code "121") (name "unconnected-(U$1B-GPIO_117-PadP9.25)") (class "Default")
      (node (ref "U$1") (pin "P9.25") (pinfunction "GPIO_117_P9.25") (pintype "bidirectional"))
    )
    (net (code "122") (name "unconnected-(U$1B-GPIO_120-PadP9.31)") (class "Default")
      (node (ref "U$1") (pin "P9.31") (pinfunction "GPIO_120_P9.31") (pintype "bidirectional"))
    )
    (net (code "123") (name "unconnected-(U$1B-GPIO_121-PadP9.29)") (class "Default")
      (node (ref "U$1") (pin "P9.29") (pinfunction "GPIO_121_P9.29") (pintype "bidirectional"))
    )
    (net (code "124") (name "unconnected-(U$1B-GPIO_122-PadP9.30)") (class "Default")
      (node (ref "U$1") (pin "P9.30") (pinfunction "GPIO_122_P9.30") (pintype "bidirectional"))
    )
    (net (code "125") (name "unconnected-(U$1B-GPIO_123-PadP9.28)") (class "Default")
      (node (ref "U$1") (pin "P9.28") (pinfunction "GPIO_123_P9.28") (pintype "bidirectional"))
    )
    (net (code "126") (name "unconnected-(U$1B-GPIO_125-PadP9.27)") (class "Default")
      (node (ref "U$1") (pin "P9.27") (pinfunction "GPIO_125_P9.27") (pintype "bidirectional"))
    )
    (net (code "127") (name "unconnected-(U$1B-I2C2_SCL-PadP9.19)") (class "Default")
      (node (ref "U$1") (pin "P9.19") (pinfunction "I2C2_SCL_P9.19") (pintype "bidirectional"))
    )
    (net (code "128") (name "unconnected-(U$1B-I2C2_SDA-PadP9.20)") (class "Default")
      (node (ref "U$1") (pin "P9.20") (pinfunction "I2C2_SDA_P9.20") (pintype "bidirectional"))
    )
    (net (code "129") (name "unconnected-(U$1B-PWR_BUT-PadP9.9)") (class "Default")
      (node (ref "U$1") (pin "P9.9") (pinfunction "PWR_BUT_P9.9") (pintype "bidirectional"))
    )
    (net (code "130") (name "unconnected-(U$1B-SYS_5V-PadP9.7)") (class "Default")
      (node (ref "U$1") (pin "P9.7") (pinfunction "SYS_5V_P9.7") (pintype "bidirectional"))
    )
    (net (code "131") (name "unconnected-(U$1B-SYS_5V-PadP9.8)") (class "Default")
      (node (ref "U$1") (pin "P9.8") (pinfunction "SYS_5V_P9.8") (pintype "bidirectional"))
    )
    (net (code "132") (name "unconnected-(U$1B-VDD_ADC-PadP9.32)") (class "Default")
      (node (ref "U$1") (pin "P9.32") (pinfunction "VDD_ADC_P9.32") (pintype "bidirectional"))
    )
  )
)
